# Page05_DDR4L_eMMC.net
KiCad netlist of a schematic drawn in Altium Designer
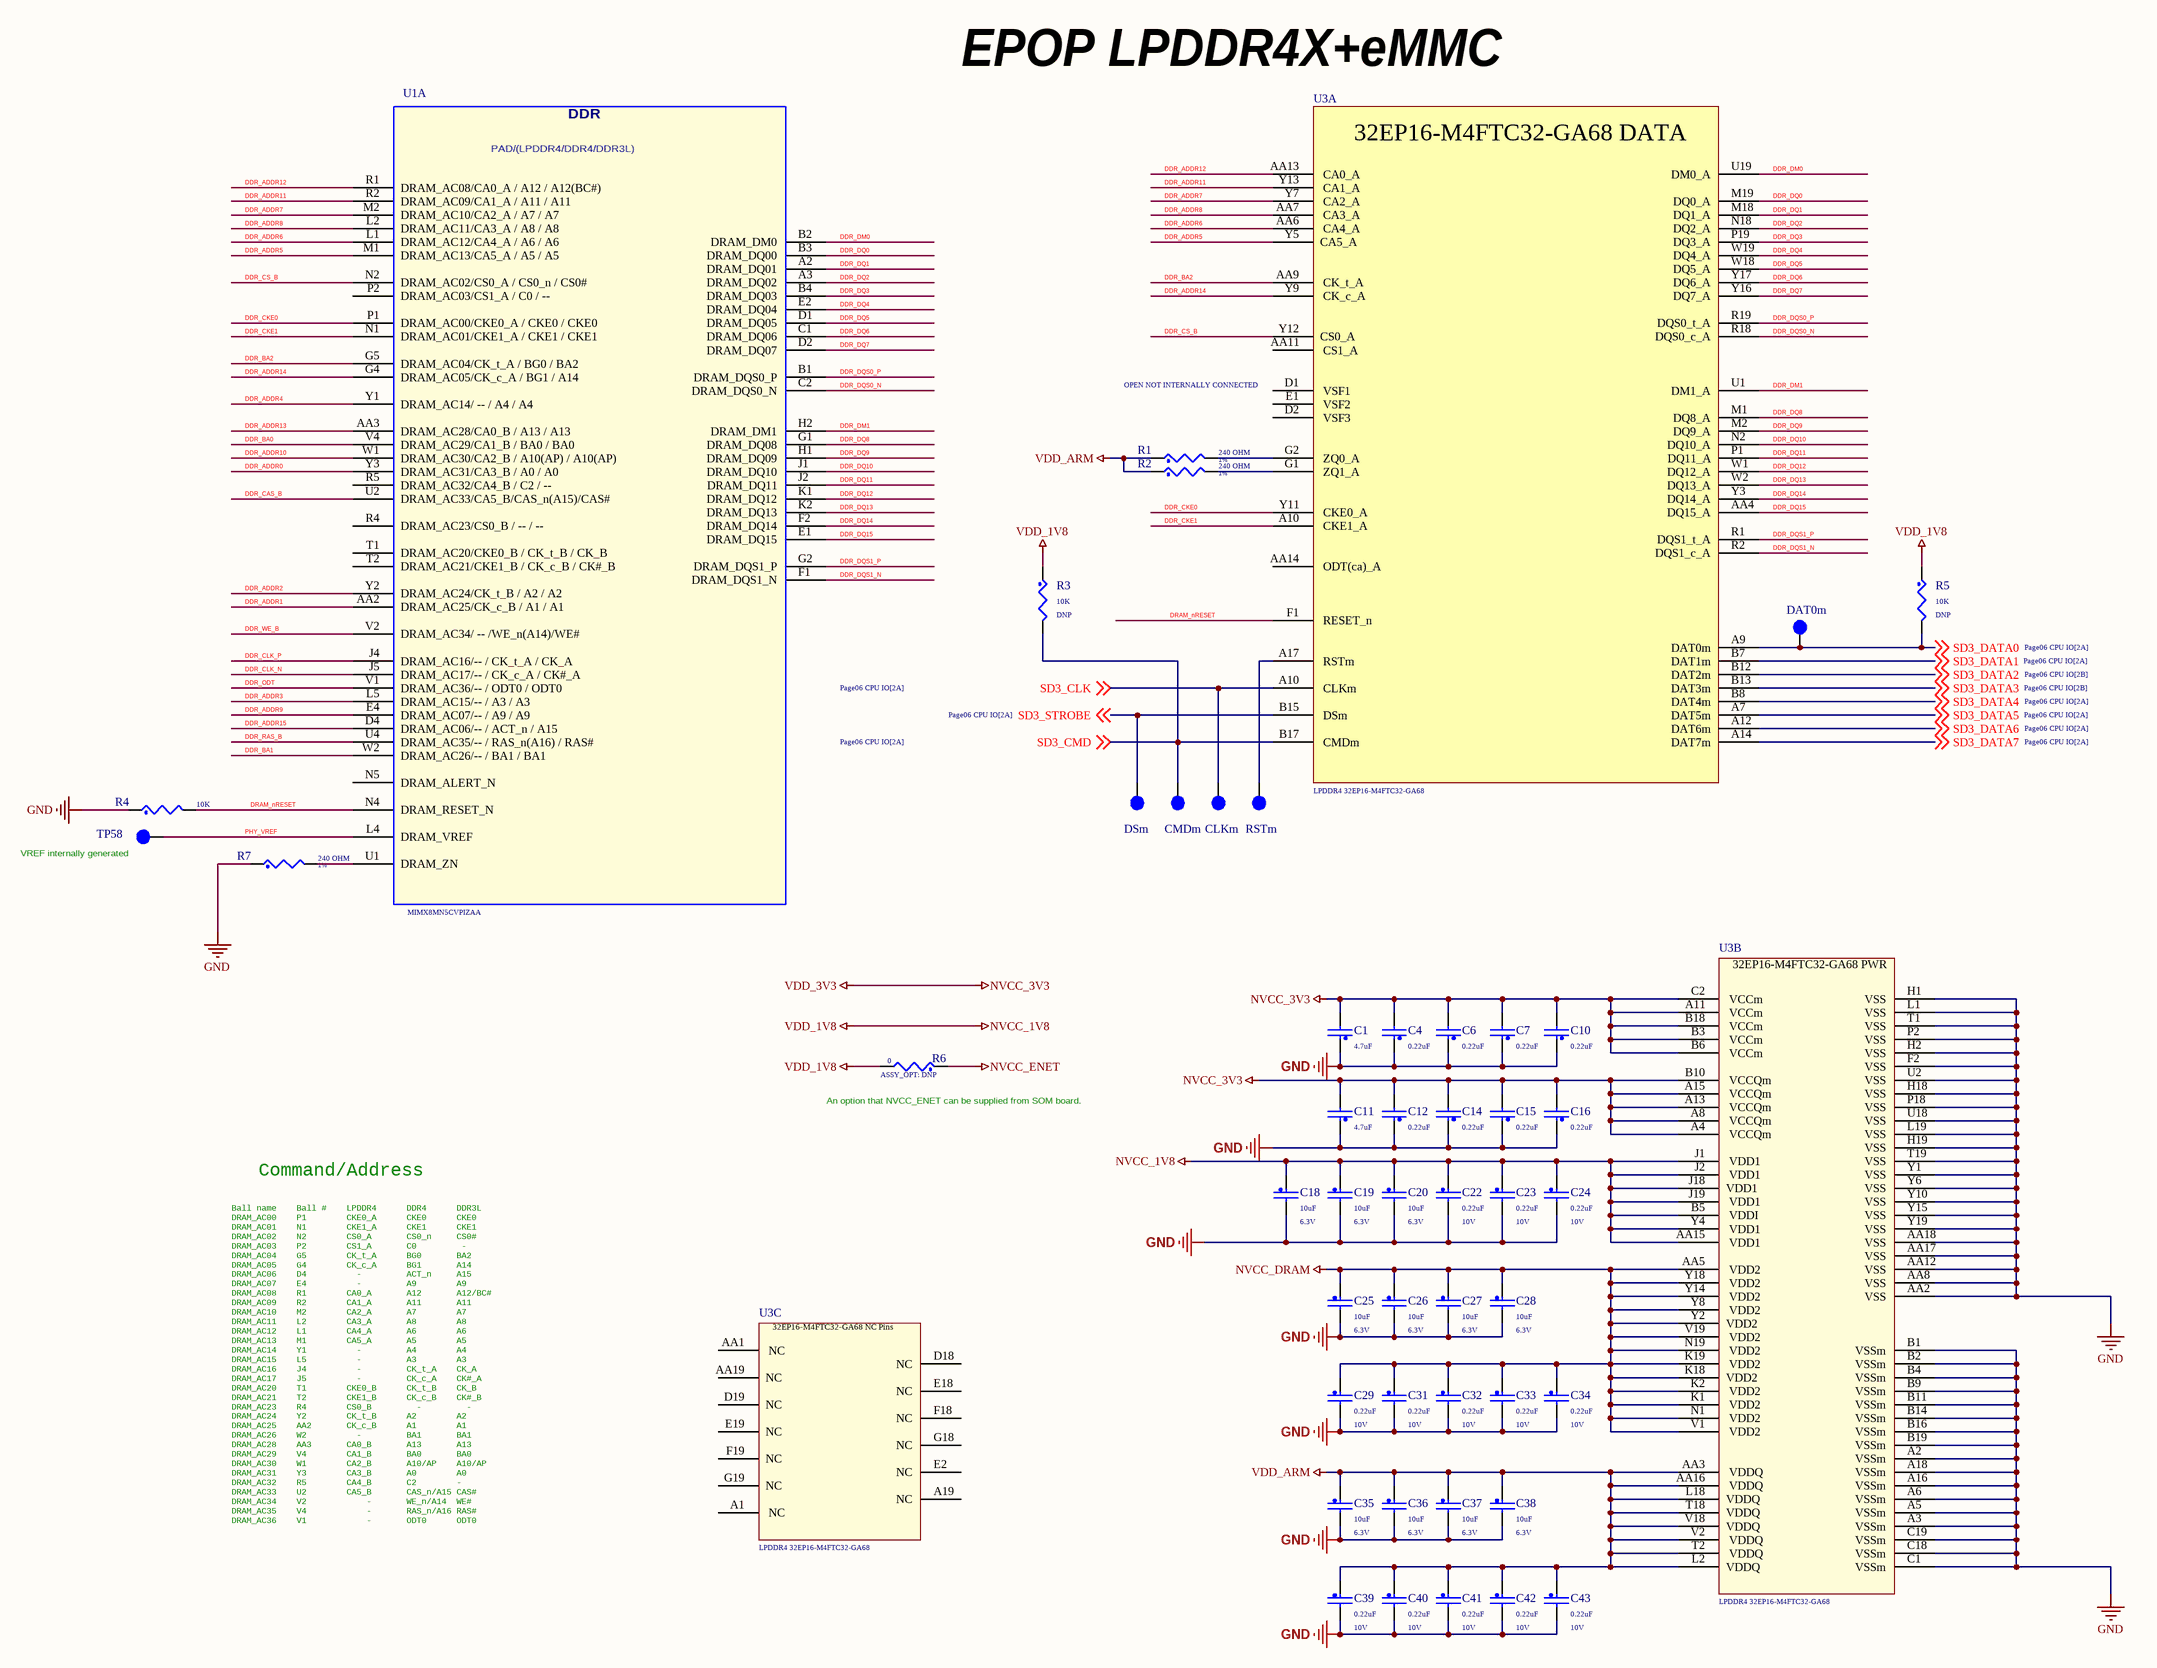
[diagram p0: Page05 DDR4L+eMMC.SchDoc]

(export (version "E")
  (design (tool "Eeschema 10.0.6"))
  (components
    (comp (ref "C1") (value "4.7uF") (footprint "0402_CC - C") (libsource (lib "AA_iMX8_M_") (part "CAP_NP")))
    (comp (ref "C4")
      (value "0.22uF")
      (footprint "0201_CC - C")
      (libsource (lib "AA_iMX8_M_") (part "CAP_NP"))
    )
    (comp (ref "C6")
      (value "0.22uF")
      (footprint "0201_CC - C")
      (libsource (lib "AA_iMX8_M_") (part "CAP_NP"))
    )
    (comp (ref "C7")
      (value "0.22uF")
      (footprint "0201_CC - C")
      (libsource (lib "AA_iMX8_M_") (part "CAP_NP"))
    )
    (comp (ref "C10")
      (value "0.22uF")
      (footprint "0201_CC - C")
      (libsource (lib "AA_iMX8_M_") (part "CAP_NP"))
    )
    (comp (ref "C11")
      (value "4.7uF")
      (footprint "0402_CC - C")
      (libsource (lib "AA_iMX8_M_") (part "CAP_NP"))
    )
    (comp (ref "C12")
      (value "0.22uF")
      (footprint "0201_CC - C")
      (libsource (lib "AA_iMX8_M_") (part "CAP_NP"))
    )
    (comp (ref "C14")
      (value "0.22uF")
      (footprint "0201_CC - C")
      (libsource (lib "AA_iMX8_M_") (part "CAP_NP"))
    )
    (comp (ref "C15")
      (value "0.22uF")
      (footprint "0201_CC - C")
      (libsource (lib "AA_iMX8_M_") (part "CAP_NP"))
    )
    (comp (ref "C16")
      (value "0.22uF")
      (footprint "0201_CC - C")
      (libsource (lib "AA_iMX8_M_") (part "CAP_NP"))
    )
    (comp (ref "C18")
      (value "10uF")
      (footprint "0402_CC - C")
      (fields (field (name "VOLTAGE") "6.3V"))
      (libsource (lib "AA_iMX8_M_") (part "CAP_NP"))
    )
    (comp (ref "C19")
      (value "10uF")
      (footprint "0402_CC - C")
      (fields (field (name "VOLTAGE") "6.3V"))
      (libsource (lib "AA_iMX8_M_") (part "CAP_NP"))
    )
    (comp (ref "C20")
      (value "10uF")
      (footprint "0402_CC - C")
      (fields (field (name "VOLTAGE") "6.3V"))
      (libsource (lib "AA_iMX8_M_") (part "CAP_NP"))
    )
    (comp (ref "C22")
      (value "0.22uF")
      (footprint "0201_CC - C")
      (fields (field (name "VOLTAGE") "10V"))
      (libsource (lib "AA_iMX8_M_") (part "CAP_NP"))
    )
    (comp (ref "C23")
      (value "0.22uF")
      (footprint "0201_CC - C")
      (fields (field (name "VOLTAGE") "10V"))
      (libsource (lib "AA_iMX8_M_") (part "CAP_NP"))
    )
    (comp (ref "C24")
      (value "0.22uF")
      (footprint "0201_CC - C")
      (fields (field (name "VOLTAGE") "10V"))
      (libsource (lib "AA_iMX8_M_") (part "CAP_NP"))
    )
    (comp (ref "C25")
      (value "10uF")
      (footprint "0402_CC - C")
      (fields (field (name "VOLTAGE") "6.3V"))
      (libsource (lib "AA_iMX8_M_") (part "CAP_NP"))
    )
    (comp (ref "C26")
      (value "10uF")
      (footprint "0402_CC - C")
      (fields (field (name "VOLTAGE") "6.3V"))
      (libsource (lib "AA_iMX8_M_") (part "CAP_NP"))
    )
    (comp (ref "C27")
      (value "10uF")
      (footprint "0402_CC - C")
      (fields (field (name "VOLTAGE") "6.3V"))
      (libsource (lib "AA_iMX8_M_") (part "CAP_NP"))
    )
    (comp (ref "C28")
      (value "10uF")
      (footprint "0402_CC - C")
      (fields (field (name "VOLTAGE") "6.3V"))
      (libsource (lib "AA_iMX8_M_") (part "CAP_NP"))
    )
    (comp (ref "C29")
      (value "0.22uF")
      (footprint "0201_CC - C")
      (fields (field (name "VOLTAGE") "10V"))
      (libsource (lib "AA_iMX8_M_") (part "CAP_NP"))
    )
    (comp (ref "C31")
      (value "0.22uF")
      (footprint "0201_CC - C")
      (fields (field (name "VOLTAGE") "10V"))
      (libsource (lib "AA_iMX8_M_") (part "CAP_NP"))
    )
    (comp (ref "C32")
      (value "0.22uF")
      (footprint "0201_CC - C")
      (fields (field (name "VOLTAGE") "10V"))
      (libsource (lib "AA_iMX8_M_") (part "CAP_NP"))
    )
    (comp (ref "C33")
      (value "0.22uF")
      (footprint "0201_CC - C")
      (fields (field (name "VOLTAGE") "10V"))
      (libsource (lib "AA_iMX8_M_") (part "CAP_NP"))
    )
    (comp (ref "C34")
      (value "0.22uF")
      (footprint "0201_CC - C")
      (fields (field (name "VOLTAGE") "10V"))
      (libsource (lib "AA_iMX8_M_") (part "CAP_NP"))
    )
    (comp (ref "C35")
      (value "10uF")
      (footprint "0402_CC - C")
      (fields (field (name "VOLTAGE") "6.3V"))
      (libsource (lib "AA_iMX8_M_") (part "CAP_NP"))
    )
    (comp (ref "C36")
      (value "10uF")
      (footprint "0402_CC - C")
      (fields (field (name "VOLTAGE") "6.3V"))
      (libsource (lib "AA_iMX8_M_") (part "CAP_NP"))
    )
    (comp (ref "C37")
      (value "10uF")
      (footprint "0402_CC - C")
      (fields (field (name "VOLTAGE") "6.3V"))
      (libsource (lib "AA_iMX8_M_") (part "CAP_NP"))
    )
    (comp (ref "C38")
      (value "10uF")
      (footprint "0402_CC - C")
      (fields (field (name "VOLTAGE") "6.3V"))
      (libsource (lib "AA_iMX8_M_") (part "CAP_NP"))
    )
    (comp (ref "C39")
      (value "0.22uF")
      (footprint "0201_CC - C")
      (fields (field (name "VOLTAGE") "10V"))
      (libsource (lib "AA_iMX8_M_") (part "CAP_NP"))
    )
    (comp (ref "C40")
      (value "0.22uF")
      (footprint "0201_CC - C")
      (fields (field (name "VOLTAGE") "10V"))
      (libsource (lib "AA_iMX8_M_") (part "CAP_NP"))
    )
    (comp (ref "C41")
      (value "0.22uF")
      (footprint "0201_CC - C")
      (fields (field (name "VOLTAGE") "10V"))
      (libsource (lib "AA_iMX8_M_") (part "CAP_NP"))
    )
    (comp (ref "C42")
      (value "0.22uF")
      (footprint "0201_CC - C")
      (fields (field (name "VOLTAGE") "10V"))
      (libsource (lib "AA_iMX8_M_") (part "CAP_NP"))
    )
    (comp (ref "C43")
      (value "0.22uF")
      (footprint "0201_CC - C")
      (fields (field (name "VOLTAGE") "10V"))
      (libsource (lib "AA_iMX8_M_") (part "CAP_NP"))
    )
    (comp (ref "CLKm")
      (value "tpad_020")
      (footprint "Test Pin")
      (description "TEST POINT PAD 0.5MM DIA SMT, NO PART TO ORDER")
      (libsource (lib "*") (part "TESTLOOP"))
    )
    (comp (ref "CMDm")
      (value "TPAD_015")
      (footprint "Test Pin")
      (description "TEST POINT PAD 15MIL DIA SMT, NO PART TO ORDER")
      (libsource (lib "*") (part "TESTLOOP"))
    )
    (comp (ref "DAT0m")
      (value "tpad_020")
      (footprint "Test Pin")
      (description "TEST POINT PAD 0.5MM DIA SMT, NO PART TO ORDER")
      (libsource (lib "*") (part "TESTLOOP"))
    )
    (comp (ref "DSm")
      (value "TPAD_015")
      (footprint "Test Pin")
      (description "TEST POINT PAD 15MIL DIA SMT, NO PART TO ORDER")
      (libsource (lib "*") (part "TESTLOOP"))
    )
    (comp (ref "R1")
      (value "240 OHM")
      (footprint "0201_RES")
      (description "RES MF 240 OHM 1/20W 1% 0201")
      (fields (field (name "VOLTAGE") "25V") (field (name "TOLERANCE") "1%"))
      (libsource (lib "*") (part "RES"))
    )
    (comp (ref "R2")
      (value "240 OHM")
      (footprint "0201_RES")
      (description "RES MF 240 OHM 1/20W 1% 0201")
      (fields (field (name "VOLTAGE") "25V") (field (name "TOLERANCE") "1%"))
      (libsource (lib "*") (part "RES"))
    )
    (comp (ref "R3")
      (value "10K")
      (footprint "0201_RES")
      (description "RES MF 10K 1/20W 5% 0201")
      (fields (field (name "ASSY_OPT") "DNP") (field (name "TOLERANCE") "5%"))
      (libsource (lib "*") (part "RES"))
    )
    (comp (ref "R4")
      (value "10K")
      (footprint "0201_RES")
      (description "RES MF 10K 1/20W 5% 0201")
      (fields (field (name "TOLERANCE") "5%"))
      (libsource (lib "*") (part "RES"))
    )
    (comp (ref "R5")
      (value "10K")
      (footprint "0201_RES")
      (description "RES MF 10K 1/20W 5% 0201")
      (fields (field (name "ASSY_OPT") "DNP") (field (name "TOLERANCE") "5%"))
      (libsource (lib "*") (part "RES"))
    )
    (comp (ref "R6")
      (value "0")
      (footprint "0402_CC_RES")
      (description "RES MF ZERO OHM 1/16W 5% 0402")
      (fields
        (field (name "ASSY_OPT") "DNP")
        (field (name "TOLERANCE") "5%")
        (field (name "VOLTAGE") "1/16W")
      )
      (libsource (lib "*") (part "RES"))
    )
    (comp (ref "R7")
      (value "240 OHM")
      (footprint "0201_RES")
      (description "RES MF 240 OHM 1/20W 1% 0201")
      (fields (field (name "VOLTAGE") "25V") (field (name "TOLERANCE") "1%"))
      (libsource (lib "*") (part "RES"))
    )
    (comp (ref "RSTm")
      (value "tpad_020")
      (footprint "Test Pin")
      (description "TEST POINT PAD 0.5MM DIA SMT, NO PART TO ORDER")
      (libsource (lib "*") (part "TESTLOOP"))
    )
    (comp (ref "TP58")
      (value "tpad_020")
      (footprint "Test Pin")
      (description "TEST POINT PAD 0.5MM DIA SMT, NO PART TO ORDER")
      (libsource (lib "*") (part "TESTLOOP"))
    )
    (comp (ref "U1")
      (value "MIMX8MN5CVPIZAA")
      (footprint "BGA306C50P21X21_1100X1100X101")
      (description "IC CPU QUAD CORTEX A53+M7 1.4GHZ -- BGA306")
      (libsource (lib "*") (part "MIMX8MN"))
    )
    (comp (ref "U3")
      (value "LPDDR4 32EP16-M4FTC32-GA68")
      (footprint "FBGA144C40P19X21_800X950X80")
      (libsource (lib "") (part "LPDDR4 32EP16-M4FTC32-GA68_1"))
    )
  )
  (nets
    (net (code "1") (name "/DDR_ADDR0") (class "Default")
      (node (ref "U1") (pin "Y3") (pinfunction "DRAM_AC31/CA3_B_/_A0_/_A0_Y3") (pintype "passive"))
    )
    (net (code "2") (name "/DDR_ADDR1") (class "Default")
      (node (ref "U1") (pin "AA2") (pinfunction "DRAM_AC25/CK_c_B_/_A1_/_A1_AA2") (pintype "passive"))
    )
    (net (code "3") (name "/DDR_ADDR2") (class "Default")
      (node (ref "U1") (pin "Y2") (pinfunction "DRAM_AC24/CK_t_B_/_A2_/_A2_Y2") (pintype "passive"))
    )
    (net (code "4") (name "/DDR_ADDR3") (class "Default")
      (node (ref "U1") (pin "L5") (pinfunction "DRAM_AC15/--_/_A3_/_A3_L5") (pintype "passive"))
    )
    (net (code "5") (name "/DDR_ADDR4") (class "Default")
      (node (ref "U1") (pin "Y1") (pinfunction "DRAM_AC14/_--_/_A4_/_A4_Y1") (pintype "passive"))
    )
    (net (code "6") (name "/DDR_ADDR5") (class "Default")
      (node (ref "U1") (pin "M1") (pinfunction "DRAM_AC13/CA5_A_/_A5_/_A5_M1") (pintype "passive"))
      (node (ref "U3") (pin "Y5") (pinfunction "CA5_A_Y5") (pintype "passive"))
    )
    (net (code "7") (name "/DDR_ADDR6") (class "Default")
      (node (ref "U1") (pin "L1") (pinfunction "DRAM_AC12/CA4_A_/_A6_/_A6_L1") (pintype "passive"))
      (node (ref "U3") (pin "AA6") (pinfunction "_CA4_A_AA6") (pintype "passive"))
    )
    (net (code "8") (name "/DDR_ADDR7") (class "Default")
      (node (ref "U1") (pin "M2") (pinfunction "DRAM_AC10/CA2_A_/_A7_/_A7_M2") (pintype "passive"))
      (node (ref "U3") (pin "Y7") (pinfunction "_CA2_A_Y7") (pintype "passive"))
    )
    (net (code "9") (name "/DDR_ADDR8") (class "Default")
      (node (ref "U1") (pin "L2") (pinfunction "DRAM_AC11/CA3_A_/_A8_/_A8_L2") (pintype "passive"))
      (node (ref "U3") (pin "AA7") (pinfunction "_CA3_A_AA7") (pintype "passive"))
    )
    (net (code "10") (name "/DDR_ADDR9") (class "Default")
      (node (ref "U1") (pin "E4") (pinfunction "DRAM_AC07/--_/_A9_/_A9_E4") (pintype "passive"))
    )
    (net (code "11") (name "/DDR_ADDR10") (class "Default")
      (node (ref "U1") (pin "W1") (pinfunction "DRAM_AC30/CA2_B_/_A10(AP)_/_A10(AP)_W1") (pintype "passive"))
    )
    (net (code "12") (name "/DDR_ADDR11") (class "Default")
      (node (ref "U1") (pin "R2") (pinfunction "DRAM_AC09/CA1_A_/_A11_/_A11_R2") (pintype "passive"))
      (node (ref "U3") (pin "Y13") (pinfunction "_CA1_A_Y13") (pintype "passive"))
    )
    (net (code "13") (name "/DDR_ADDR12") (class "Default")
      (node (ref "U1") (pin "R1") (pinfunction "DRAM_AC08/CA0_A_/_A12_/_A12(BC#)_R1") (pintype "passive"))
      (node (ref "U3") (pin "AA13") (pinfunction "_CA0_A_AA13") (pintype "passive"))
    )
    (net (code "14") (name "/DDR_ADDR13") (class "Default")
      (node (ref "U1") (pin "AA3") (pinfunction "DRAM_AC28/CA0_B_/_A13_/_A13_AA3") (pintype "passive"))
    )
    (net (code "15") (name "/DDR_ADDR14") (class "Default")
      (node (ref "U1") (pin "G4") (pinfunction "DRAM_AC05/CK_c_A_/_BG1_/_A14_G4") (pintype "passive"))
      (node (ref "U3") (pin "Y9") (pinfunction "_CK_c_A_Y9") (pintype "passive"))
    )
    (net (code "16") (name "/DDR_ADDR15") (class "Default")
      (node (ref "U1") (pin "D4") (pinfunction "DRAM_AC06/--_/_ACT_n_/_A15_D4") (pintype "passive"))
    )
    (net (code "17") (name "/DDR_BA0") (class "Default")
      (node (ref "U1") (pin "V4") (pinfunction "DRAM_AC29/CA1_B_/_BA0_/_BA0_V4") (pintype "passive"))
    )
    (net (code "18") (name "/DDR_BA1") (class "Default")
      (node (ref "U1") (pin "W2") (pinfunction "DRAM_AC26/--_/_BA1_/_BA1_W2") (pintype "passive"))
    )
    (net (code "19") (name "/DDR_BA2") (class "Default")
      (node (ref "U1") (pin "G5") (pinfunction "DRAM_AC04/CK_t_A_/_BG0_/_BA2_G5") (pintype "passive"))
      (node (ref "U3") (pin "AA9") (pinfunction "_CK_t_A_AA9") (pintype "passive"))
    )
    (net (code "20") (name "/DDR_CAS_B") (class "Default")
      (node (ref "U1") (pin "U2") (pinfunction "DRAM_AC33/CA5_B/CAS_n(A15)/CAS#_U2") (pintype "passive"))
    )
    (net (code "21") (name "/DDR_CKE0") (class "Default")
      (node (ref "U1") (pin "P1") (pinfunction "DRAM_AC00/CKE0_A_/_CKE0_/_CKE0_P1") (pintype "passive"))
      (node (ref "U3") (pin "Y11") (pinfunction "_CKE0_A_Y11") (pintype "passive"))
    )
    (net (code "22") (name "/DDR_CKE1") (class "Default")
      (node (ref "U1") (pin "N1") (pinfunction "DRAM_AC01/CKE1_A_/_CKE1_/_CKE1_N1") (pintype "passive"))
      (node (ref "U3") (pin "A10") (pinfunction "_CKE1_A_A10") (pintype "passive"))
    )
    (net (code "23") (name "/DDR_CLK_N") (class "Default")
      (node (ref "U1") (pin "J5") (pinfunction "DRAM_AC17/--_/_CK_c_A_/_CK#_A_J5") (pintype "passive"))
    )
    (net (code "24") (name "/DDR_CLK_P") (class "Default")
      (node (ref "U1") (pin "J4") (pinfunction "DRAM_AC16/--_/_CK_t_A_/_CK_A_J4") (pintype "passive"))
    )
    (net (code "25") (name "/DDR_CS_B") (class "Default")
      (node (ref "U1") (pin "N2") (pinfunction "DRAM_AC02/CS0_A_/_CS0_n_/_CS0#_N2") (pintype "passive"))
      (node (ref "U3") (pin "Y12") (pinfunction "CS0_A_Y12") (pintype "passive"))
    )
    (net (code "26") (name "/DDR_DM0") (class "Default")
      (node (ref "U1") (pin "B2") (pinfunction "DRAM_DM0_B2") (pintype "passive"))
      (node (ref "U3") (pin "U19") (pinfunction "_DM0_A_U19") (pintype "passive"))
    )
    (net (code "27") (name "/DDR_DM1") (class "Default")
      (node (ref "U1") (pin "H2") (pinfunction "DRAM_DM1_H2") (pintype "passive"))
      (node (ref "U3") (pin "U1") (pinfunction "_DM1_A_U1") (pintype "passive"))
    )
    (net (code "28") (name "/DDR_DQ0") (class "Default")
      (node (ref "U1") (pin "B3") (pinfunction "DRAM_DQ00_B3") (pintype "passive"))
      (node (ref "U3") (pin "M19") (pinfunction "_DQ0_A_M19") (pintype "passive"))
    )
    (net (code "29") (name "/DDR_DQ1") (class "Default")
      (node (ref "U1") (pin "A2") (pinfunction "DRAM_DQ01_A2") (pintype "passive"))
      (node (ref "U3") (pin "M18") (pinfunction "DQ1_A_M18") (pintype "passive"))
    )
    (net (code "30") (name "/DDR_DQ2") (class "Default")
      (node (ref "U1") (pin "A3") (pinfunction "DRAM_DQ02_A3") (pintype "passive"))
      (node (ref "U3") (pin "N18") (pinfunction "DQ2_A_N18") (pintype "passive"))
    )
    (net (code "31") (name "/DDR_DQ3") (class "Default")
      (node (ref "U1") (pin "B4") (pinfunction "DRAM_DQ03_B4") (pintype "passive"))
      (node (ref "U3") (pin "P19") (pinfunction "DQ3_A_P19") (pintype "passive"))
    )
    (net (code "32") (name "/DDR_DQ4") (class "Default")
      (node (ref "U1") (pin "E2") (pinfunction "DRAM_DQ04_E2") (pintype "passive"))
      (node (ref "U3") (pin "W19") (pinfunction "_DQ4_A_W19") (pintype "passive"))
    )
    (net (code "33") (name "/DDR_DQ5") (class "Default")
      (node (ref "U1") (pin "D1") (pinfunction "DRAM_DQ05_D1") (pintype "passive"))
      (node (ref "U3") (pin "W18") (pinfunction "DQ5_A_W18") (pintype "passive"))
    )
    (net (code "34") (name "/DDR_DQ6") (class "Default")
      (node (ref "U1") (pin "C1") (pinfunction "DRAM_DQ06_C1") (pintype "passive"))
      (node (ref "U3") (pin "Y17") (pinfunction "_DQ6_A_Y17") (pintype "passive"))
    )
    (net (code "35") (name "/DDR_DQ7") (class "Default")
      (node (ref "U1") (pin "D2") (pinfunction "DRAM_DQ07_D2") (pintype "passive"))
      (node (ref "U3") (pin "Y16") (pinfunction "_DQ7_A_Y16") (pintype "passive"))
    )
    (net (code "36") (name "/DDR_DQ8") (class "Default")
      (node (ref "U1") (pin "G1") (pinfunction "DRAM_DQ08_G1") (pintype "passive"))
      (node (ref "U3") (pin "M1") (pinfunction "_DQ8_A_M1") (pintype "passive"))
    )
    (net (code "37") (name "/DDR_DQ9") (class "Default")
      (node (ref "U1") (pin "H1") (pinfunction "DRAM_DQ09_H1") (pintype "passive"))
      (node (ref "U3") (pin "M2") (pinfunction "_DQ9_A_M2") (pintype "passive"))
    )
    (net (code "38") (name "/DDR_DQ10") (class "Default")
      (node (ref "U1") (pin "J1") (pinfunction "DRAM_DQ10_J1") (pintype "passive"))
      (node (ref "U3") (pin "N2") (pinfunction "_DQ10_A_N2") (pintype "passive"))
    )
    (net (code "39") (name "/DDR_DQ11") (class "Default")
      (node (ref "U1") (pin "J2") (pinfunction "DRAM_DQ11_J2") (pintype "passive"))
      (node (ref "U3") (pin "P1") (pinfunction "_DQ11_A_P1") (pintype "passive"))
    )
    (net (code "40") (name "/DDR_DQ12") (class "Default")
      (node (ref "U1") (pin "K1") (pinfunction "DRAM_DQ12_K1") (pintype "passive"))
      (node (ref "U3") (pin "W1") (pinfunction "_DQ12_A_W1") (pintype "passive"))
    )
    (net (code "41") (name "/DDR_DQ13") (class "Default")
      (node (ref "U1") (pin "K2") (pinfunction "DRAM_DQ13_K2") (pintype "passive"))
      (node (ref "U3") (pin "W2") (pinfunction "_DQ13_A_W2") (pintype "passive"))
    )
    (net (code "42") (name "/DDR_DQ14") (class "Default")
      (node (ref "U1") (pin "F2") (pinfunction "DRAM_DQ14_F2") (pintype "passive"))
      (node (ref "U3") (pin "Y3") (pinfunction "_DQ14_A_Y3") (pintype "passive"))
    )
    (net (code "43") (name "/DDR_DQ15") (class "Default")
      (node (ref "U1") (pin "E1") (pinfunction "DRAM_DQ15_E1") (pintype "passive"))
      (node (ref "U3") (pin "AA4") (pinfunction "_DQ15_A_AA4") (pintype "passive"))
    )
    (net (code "44") (name "/DDR_DQS0_N") (class "Default")
      (node (ref "U1") (pin "C2") (pinfunction "DRAM_DQS0_N_C2") (pintype "passive"))
      (node (ref "U3") (pin "R18") (pinfunction "DQS0_c_A_R18") (pintype "passive"))
    )
    (net (code "45") (name "/DDR_DQS0_P") (class "Default")
      (node (ref "U1") (pin "B1") (pinfunction "DRAM_DQS0_P_B1") (pintype "passive"))
      (node (ref "U3") (pin "R19") (pinfunction "_DQS0_t_A_R19") (pintype "passive"))
    )
    (net (code "46") (name "/DDR_DQS1_N") (class "Default")
      (node (ref "U1") (pin "F1") (pinfunction "DRAM_DQS1_N_F1") (pintype "passive"))
      (node (ref "U3") (pin "R2") (pinfunction "_DQS1_c_A_R2") (pintype "passive"))
    )
    (net (code "47") (name "/DDR_DQS1_P") (class "Default")
      (node (ref "U1") (pin "G2") (pinfunction "DRAM_DQS1_P_G2") (pintype "passive"))
      (node (ref "U3") (pin "R1") (pinfunction "_DQS1_t_A_R1") (pintype "passive"))
    )
    (net (code "48") (name "/DDR_ODT") (class "Default")
      (node (ref "U1") (pin "V1") (pinfunction "DRAM_AC36/--_/_ODT0_/_ODT0_V1") (pintype "passive"))
    )
    (net (code "49") (name "/DDR_RAS_B") (class "Default")
      (node (ref "U1") (pin "U4") (pinfunction "DRAM_AC35/--_/_RAS_n(A16)_/_RAS#_U4") (pintype "passive"))
    )
    (net (code "50") (name "/DDR_WE_B") (class "Default")
      (node (ref "U1") (pin "V2") (pinfunction "DRAM_AC34/_--_/WE_n(A14)/WE#_V2") (pintype "passive"))
    )
    (net (code "51") (name "/DRAM_nRESET") (class "Default")
      (node (ref "R4") (pin "2") (pinfunction "2_2") (pintype "passive"))
      (node (ref "U1") (pin "N4") (pinfunction "DRAM_RESET_N_N4") (pintype "passive"))
      (node (ref "U3") (pin "F1") (pinfunction "_RESET_n_F1") (pintype "passive"))
    )
    (net (code "52") (name "/PHY_VREF") (class "Default")
      (node (ref "TP58") (pin "1") (pinfunction "Pin1_1") (pintype "passive"))
      (node (ref "U1") (pin "L4") (pinfunction "DRAM_VREF_L4") (pintype "passive"))
    )
    (net (code "53") (name "GND") (class "Default")
      (node (ref "C1") (pin "1") (pinfunction "1_1") (pintype "passive"))
      (node (ref "C10") (pin "1") (pinfunction "1_1") (pintype "passive"))
      (node (ref "C11") (pin "1") (pinfunction "1_1") (pintype "passive"))
      (node (ref "C12") (pin "1") (pinfunction "1_1") (pintype "passive"))
      (node (ref "C14") (pin "1") (pinfunction "1_1") (pintype "passive"))
      (node (ref "C15") (pin "1") (pinfunction "1_1") (pintype "passive"))
      (node (ref "C16") (pin "1") (pinfunction "1_1") (pintype "passive"))
      (node (ref "C18") (pin "2") (pinfunction "2_2") (pintype "passive"))
      (node (ref "C19") (pin "2") (pinfunction "2_2") (pintype "passive"))
      (node (ref "C20") (pin "2") (pinfunction "2_2") (pintype "passive"))
      (node (ref "C22") (pin "2") (pinfunction "2_2") (pintype "passive"))
      (node (ref "C23") (pin "2") (pinfunction "2_2") (pintype "passive"))
      (node (ref "C24") (pin "2") (pinfunction "2_2") (pintype "passive"))
      (node (ref "C25") (pin "2") (pinfunction "2_2") (pintype "passive"))
      (node (ref "C26") (pin "2") (pinfunction "2_2") (pintype "passive"))
      (node (ref "C27") (pin "2") (pinfunction "2_2") (pintype "passive"))
      (node (ref "C28") (pin "2") (pinfunction "2_2") (pintype "passive"))
      (node (ref "C29") (pin "2") (pinfunction "2_2") (pintype "passive"))
      (node (ref "C31") (pin "2") (pinfunction "2_2") (pintype "passive"))
      (node (ref "C32") (pin "2") (pinfunction "2_2") (pintype "passive"))
      (node (ref "C33") (pin "2") (pinfunction "2_2") (pintype "passive"))
      (node (ref "C34") (pin "2") (pinfunction "2_2") (pintype "passive"))
      (node (ref "C35") (pin "2") (pinfunction "2_2") (pintype "passive"))
      (node (ref "C36") (pin "2") (pinfunction "2_2") (pintype "passive"))
      (node (ref "C37") (pin "2") (pinfunction "2_2") (pintype "passive"))
      (node (ref "C38") (pin "2") (pinfunction "2_2") (pintype "passive"))
      (node (ref "C39") (pin "2") (pinfunction "2_2") (pintype "passive"))
      (node (ref "C4") (pin "1") (pinfunction "1_1") (pintype "passive"))
      (node (ref "C40") (pin "2") (pinfunction "2_2") (pintype "passive"))
      (node (ref "C41") (pin "2") (pinfunction "2_2") (pintype "passive"))
      (node (ref "C42") (pin "2") (pinfunction "2_2") (pintype "passive"))
      (node (ref "C43") (pin "2") (pinfunction "2_2") (pintype "passive"))
      (node (ref "C6") (pin "1") (pinfunction "1_1") (pintype "passive"))
      (node (ref "C7") (pin "1") (pinfunction "1_1") (pintype "passive"))
      (node (ref "R4") (pin "1") (pinfunction "1_1") (pintype "passive"))
      (node (ref "R7") (pin "1") (pinfunction "1_1") (pintype "passive"))
      (node (ref "U3") (pin "A16") (pinfunction "_VSSm_A16") (pintype "power_in"))
      (node (ref "U3") (pin "A18") (pinfunction "_VSSm_A18") (pintype "power_in"))
      (node (ref "U3") (pin "A2") (pinfunction "_VSSm_A2") (pintype "power_in"))
      (node (ref "U3") (pin "A3") (pinfunction "VSSm_A3") (pintype "power_in"))
      (node (ref "U3") (pin "A5") (pinfunction "_VSSm_A5") (pintype "power_in"))
      (node (ref "U3") (pin "A6") (pinfunction "_VSSm_A6") (pintype "power_in"))
      (node (ref "U3") (pin "AA12") (pinfunction "_VSS_AA12") (pintype "power_in"))
      (node (ref "U3") (pin "AA17") (pinfunction "_VSS_AA17") (pintype "power_in"))
      (node (ref "U3") (pin "AA18") (pinfunction "VSS_AA18") (pintype "power_in"))
      (node (ref "U3") (pin "AA2") (pinfunction "VSS_AA2") (pintype "power_in"))
      (node (ref "U3") (pin "AA8") (pinfunction "_VSS_AA8") (pintype "power_in"))
      (node (ref "U3") (pin "B1") (pinfunction "_VSSm_B1") (pintype "power_in"))
      (node (ref "U3") (pin "B11") (pinfunction "_VSSm_B11") (pintype "power_in"))
      (node (ref "U3") (pin "B14") (pinfunction "_VSSm_B14") (pintype "power_in"))
      (node (ref "U3") (pin "B16") (pinfunction "_VSSm_B16") (pintype "power_in"))
      (node (ref "U3") (pin "B19") (pinfunction "_VSSm_B19") (pintype "power_in"))
      (node (ref "U3") (pin "B2") (pinfunction "_VSSm_B2") (pintype "power_in"))
      (node (ref "U3") (pin "B4") (pinfunction "_VSSm_B4") (pintype "power_in"))
      (node (ref "U3") (pin "B9") (pinfunction "_VSSm_B9") (pintype "power_in"))
      (node (ref "U3") (pin "C1") (pinfunction "_VSSm_C1") (pintype "power_in"))
      (node (ref "U3") (pin "C18") (pinfunction "VSSm_C18") (pintype "power_in"))
      (node (ref "U3") (pin "C19") (pinfunction "_VSSm_C19") (pintype "power_in"))
      (node (ref "U3") (pin "F2") (pinfunction "_VSS_F2") (pintype "power_in"))
      (node (ref "U3") (pin "H1") (pinfunction "_VSS_H1") (pintype "power_in"))
      (node (ref "U3") (pin "H18") (pinfunction "VSS_H18") (pintype "power_in"))
      (node (ref "U3") (pin "H19") (pinfunction "VSS_H19") (pintype "power_in"))
      (node (ref "U3") (pin "H2") (pinfunction "VSS_H2") (pintype "power_in"))
      (node (ref "U3") (pin "L1") (pinfunction "_VSS_L1") (pintype "power_in"))
      (node (ref "U3") (pin "L19") (pinfunction "VSS_L19") (pintype "power_in"))
      (node (ref "U3") (pin "P18") (pinfunction "VSS_P18") (pintype "power_in"))
      (node (ref "U3") (pin "P2") (pinfunction "_VSS_P2") (pintype "power_in"))
      (node (ref "U3") (pin "T1") (pinfunction "_VSS_T1") (pintype "power_in"))
      (node (ref "U3") (pin "T19") (pinfunction "VSS_T19") (pintype "power_in"))
      (node (ref "U3") (pin "U18") (pinfunction "VSS_U18") (pintype "power_in"))
      (node (ref "U3") (pin "U2") (pinfunction "_VSS_U2") (pintype "power_in"))
      (node (ref "U3") (pin "Y1") (pinfunction "_VSS_Y1") (pintype "power_in"))
      (node (ref "U3") (pin "Y10") (pinfunction "_VSS_Y10") (pintype "power_in"))
      (node (ref "U3") (pin "Y15") (pinfunction "_VSS_Y15") (pintype "power_in"))
      (node (ref "U3") (pin "Y19") (pinfunction "VSS_Y19") (pintype "power_in"))
      (node (ref "U3") (pin "Y6") (pinfunction "_VSS_Y6") (pintype "power_in"))
    )
    (net (code "54") (name "NVCC_1V8") (class "Default")
      (node (ref "C18") (pin "1") (pinfunction "1_1") (pintype "passive"))
      (node (ref "C19") (pin "1") (pinfunction "1_1") (pintype "passive"))
      (node (ref "C20") (pin "1") (pinfunction "1_1") (pintype "passive"))
      (node (ref "C22") (pin "1") (pinfunction "1_1") (pintype "passive"))
      (node (ref "C23") (pin "1") (pinfunction "1_1") (pintype "passive"))
      (node (ref "C24") (pin "1") (pinfunction "1_1") (pintype "passive"))
      (node (ref "R3") (pin "1") (pinfunction "1_1") (pintype "passive"))
      (node (ref "R5") (pin "1") (pinfunction "1_1") (pintype "passive"))
      (node (ref "R6") (pin "2") (pinfunction "2_2") (pintype "passive"))
      (node (ref "U3") (pin "AA15") (pinfunction "_VDD1_AA15") (pintype "power_in"))
      (node (ref "U3") (pin "B5") (pinfunction "_VDDI_B5") (pintype "power_in"))
      (node (ref "U3") (pin "J1") (pinfunction "_VDD1_J1") (pintype "power_in"))
      (node (ref "U3") (pin "J18") (pinfunction "VDD1_J18") (pintype "power_in"))
      (node (ref "U3") (pin "J19") (pinfunction "_VDD1_J19") (pintype "power_in"))
      (node (ref "U3") (pin "J2") (pinfunction "_VDD1_J2") (pintype "power_in"))
      (node (ref "U3") (pin "Y4") (pinfunction "_VDD1_Y4") (pintype "power_in"))
    )
    (net (code "55") (name "NVCC_3V3") (class "Default")
      (node (ref "C1") (pin "2") (pinfunction "2_2") (pintype "passive"))
      (node (ref "C10") (pin "2") (pinfunction "2_2") (pintype "passive"))
      (node (ref "C11") (pin "2") (pinfunction "2_2") (pintype "passive"))
      (node (ref "C12") (pin "2") (pinfunction "2_2") (pintype "passive"))
      (node (ref "C14") (pin "2") (pinfunction "2_2") (pintype "passive"))
      (node (ref "C15") (pin "2") (pinfunction "2_2") (pintype "passive"))
      (node (ref "C16") (pin "2") (pinfunction "2_2") (pintype "passive"))
      (node (ref "C4") (pin "2") (pinfunction "2_2") (pintype "passive"))
      (node (ref "C6") (pin "2") (pinfunction "2_2") (pintype "passive"))
      (node (ref "C7") (pin "2") (pinfunction "2_2") (pintype "passive"))
      (node (ref "U3") (pin "A11") (pinfunction "_VCCm_A11") (pintype "power_in"))
      (node (ref "U3") (pin "A13") (pinfunction "_VCCQm_A13") (pintype "power_in"))
      (node (ref "U3") (pin "A15") (pinfunction "_VCCQm_A15") (pintype "power_in"))
      (node (ref "U3") (pin "A4") (pinfunction "_VCCQm_A4") (pintype "power_in"))
      (node (ref "U3") (pin "A8") (pinfunction "_VCCQm_A8") (pintype "power_in"))
      (node (ref "U3") (pin "B10") (pinfunction "_VCCQm_B10") (pintype "power_in"))
      (node (ref "U3") (pin "B18") (pinfunction "_VCCm_B18") (pintype "power_in"))
      (node (ref "U3") (pin "B3") (pinfunction "_VCCm_B3") (pintype "power_in"))
      (node (ref "U3") (pin "B6") (pinfunction "_VCCm_B6") (pintype "power_in"))
      (node (ref "U3") (pin "C2") (pinfunction "_VCCm_C2") (pintype "power_in"))
    )
    (net (code "56") (name "NVCC_DRAM") (class "Default")
      (node (ref "C25") (pin "1") (pinfunction "1_1") (pintype "passive"))
      (node (ref "C26") (pin "1") (pinfunction "1_1") (pintype "passive"))
      (node (ref "C27") (pin "1") (pinfunction "1_1") (pintype "passive"))
      (node (ref "C28") (pin "1") (pinfunction "1_1") (pintype "passive"))
      (node (ref "C29") (pin "1") (pinfunction "1_1") (pintype "passive"))
      (node (ref "C31") (pin "1") (pinfunction "1_1") (pintype "passive"))
      (node (ref "C32") (pin "1") (pinfunction "1_1") (pintype "passive"))
      (node (ref "C33") (pin "1") (pinfunction "1_1") (pintype "passive"))
      (node (ref "C34") (pin "1") (pinfunction "1_1") (pintype "passive"))
      (node (ref "U3") (pin "AA5") (pinfunction "_VDD2_AA5") (pintype "power_in"))
      (node (ref "U3") (pin "K1") (pinfunction "_VDD2_K1") (pintype "power_in"))
      (node (ref "U3") (pin "K18") (pinfunction "VDD2_K18") (pintype "power_in"))
      (node (ref "U3") (pin "K19") (pinfunction "_VDD2_K19") (pintype "power_in"))
      (node (ref "U3") (pin "K2") (pinfunction "_VDD2_K2") (pintype "power_in"))
      (node (ref "U3") (pin "N1") (pinfunction "_VDD2_N1") (pintype "power_in"))
      (node (ref "U3") (pin "N19") (pinfunction "_VDD2_N19") (pintype "power_in"))
      (node (ref "U3") (pin "V1") (pinfunction "_VDD2_V1") (pintype "power_in"))
      (node (ref "U3") (pin "V19") (pinfunction "_VDD2_V19") (pintype "power_in"))
      (node (ref "U3") (pin "Y14") (pinfunction "_VDD2_Y14") (pintype "power_in"))
      (node (ref "U3") (pin "Y18") (pinfunction "_VDD2_Y18") (pintype "power_in"))
      (node (ref "U3") (pin "Y2") (pinfunction "VDD2_Y2") (pintype "power_in"))
      (node (ref "U3") (pin "Y8") (pinfunction "_VDD2_Y8") (pintype "power_in"))
    )
    (net (code "57") (name "NVCC_ENET") (class "Default")
      (node (ref "R6") (pin "1") (pinfunction "1_1") (pintype "passive"))
    )
    (net (code "58") (name "Net-(RSTm-Pin1)") (class "Default")
      (node (ref "RSTm") (pin "1") (pinfunction "Pin1_1") (pintype "passive"))
      (node (ref "U3") (pin "A17") (pinfunction "_RSTm_A17") (pintype "passive"))
    )
    (net (code "59") (name "Net-(U1A-DRAM_ZN)") (class "Default")
      (node (ref "R7") (pin "2") (pinfunction "2_2") (pintype "passive"))
      (node (ref "U1") (pin "U1") (pinfunction "DRAM_ZN_U1") (pintype "passive"))
    )
    (net (code "60") (name "Net-(U3A-_ZQ0_A)") (class "Default")
      (node (ref "R1") (pin "2") (pinfunction "2_2") (pintype "passive"))
      (node (ref "U3") (pin "G2") (pinfunction "_ZQ0_A_G2") (pintype "passive"))
    )
    (net (code "61") (name "Net-(U3A-_ZQ1_A)") (class "Default")
      (node (ref "R2") (pin "2") (pinfunction "2_2") (pintype "passive"))
      (node (ref "U3") (pin "G1") (pinfunction "_ZQ1_A_G1") (pintype "passive"))
    )
    (net (code "62") (name "SD3_CLK") (class "Default")
      (node (ref "CLKm") (pin "1") (pinfunction "Pin1_1") (pintype "passive"))
      (node (ref "U3") (pin "A10") (pinfunction "_CLKm_A10") (pintype "passive"))
    )
    (net (code "63") (name "SD3_CMD") (class "Default")
      (node (ref "CMDm") (pin "1") (pinfunction "Pin1_1") (pintype "passive"))
      (node (ref "R3") (pin "2") (pinfunction "2_2") (pintype "passive"))
      (node (ref "U3") (pin "B17") (pinfunction "_CMDm_B17") (pintype "passive"))
    )
    (net (code "64") (name "SD3_DATA0") (class "Default")
      (node (ref "DAT0m") (pin "1") (pinfunction "Pin1_1") (pintype "passive"))
      (node (ref "R5") (pin "2") (pinfunction "2_2") (pintype "passive"))
      (node (ref "U3") (pin "A9") (pinfunction "_DAT0m_A9") (pintype "passive"))
    )
    (net (code "65") (name "SD3_DATA1") (class "Default")
      (node (ref "U3") (pin "B7") (pinfunction "DAT1m_B7") (pintype "passive"))
    )
    (net (code "66") (name "SD3_DATA2") (class "Default")
      (node (ref "U3") (pin "B12") (pinfunction "_DAT2m_B12") (pintype "passive"))
    )
    (net (code "67") (name "SD3_DATA3") (class "Default")
      (node (ref "U3") (pin "B13") (pinfunction "_DAT3m_B13") (pintype "passive"))
    )
    (net (code "68") (name "SD3_DATA4") (class "Default")
      (node (ref "U3") (pin "B8") (pinfunction "_DAT4m_B8") (pintype "passive"))
    )
    (net (code "69") (name "SD3_DATA5") (class "Default")
      (node (ref "U3") (pin "A7") (pinfunction "_DAT5m_A7") (pintype "passive"))
    )
    (net (code "70") (name "SD3_DATA6") (class "Default")
      (node (ref "U3") (pin "A12") (pinfunction "_DAT6m_A12") (pintype "passive"))
    )
    (net (code "71") (name "SD3_DATA7") (class "Default")
      (node (ref "U3") (pin "A14") (pinfunction "_DAT7m_A14") (pintype "passive"))
    )
    (net (code "72") (name "SD3_STROBE") (class "Default")
      (node (ref "DSm") (pin "1") (pinfunction "Pin1_1") (pintype "passive"))
      (node (ref "U3") (pin "B15") (pinfunction "_DSm_B15") (pintype "passive"))
    )
    (net (code "73") (name "VDD_ARM") (class "Default")
      (node (ref "C35") (pin "1") (pinfunction "1_1") (pintype "passive"))
      (node (ref "C36") (pin "1") (pinfunction "1_1") (pintype "passive"))
      (node (ref "C37") (pin "1") (pinfunction "1_1") (pintype "passive"))
      (node (ref "C38") (pin "1") (pinfunction "1_1") (pintype "passive"))
      (node (ref "C39") (pin "1") (pinfunction "1_1") (pintype "passive"))
      (node (ref "C40") (pin "1") (pinfunction "1_1") (pintype "passive"))
      (node (ref "C41") (pin "1") (pinfunction "1_1") (pintype "passive"))
      (node (ref "C42") (pin "1") (pinfunction "1_1") (pintype "passive"))
      (node (ref "C43") (pin "1") (pinfunction "1_1") (pintype "passive"))
      (node (ref "R1") (pin "1") (pinfunction "1_1") (pintype "passive"))
      (node (ref "R2") (pin "1") (pinfunction "1_1") (pintype "passive"))
      (node (ref "U3") (pin "AA16") (pinfunction "_VDDQ_AA16") (pintype "power_in"))
      (node (ref "U3") (pin "AA3") (pinfunction "_VDDQ_AA3") (pintype "power_in"))
      (node (ref "U3") (pin "L18") (pinfunction "VDDQ_L18") (pintype "power_in"))
      (node (ref "U3") (pin "L2") (pinfunction "VDDQ_L2") (pintype "power_in"))
      (node (ref "U3") (pin "T18") (pinfunction "VDDQ_T18") (pintype "power_in"))
      (node (ref "U3") (pin "T2") (pinfunction "_VDDQ_T2") (pintype "power_in"))
      (node (ref "U3") (pin "V18") (pinfunction "VDDQ_V18") (pintype "power_in"))
      (node (ref "U3") (pin "V2") (pinfunction "_VDDQ_V2") (pintype "power_in"))
    )
    (net (code "74") (name "unconnected-(U1A-DRAM_AC03{slash}CS1_A_{slash}_C0_{slash}_---PadP2)") (class "Default")
      (node (ref "U1") (pin "P2") (pinfunction "DRAM_AC03/CS1_A_/_C0_/_--_P2") (pintype "passive"))
    )
    (net (code "75") (name "unconnected-(U1A-DRAM_AC20{slash}CKE0_B_{slash}_CK_t_B_{slash}_CK_B-PadT1)") (class "Default")
      (node (ref "U1") (pin "T1") (pinfunction "DRAM_AC20/CKE0_B_/_CK_t_B_/_CK_B_T1") (pintype "passive"))
    )
    (net (code "76") (name "unconnected-(U1A-DRAM_AC21{slash}CKE1_B_{slash}_CK_c_B_{slash}_CK#_B-PadT2)") (class "Default")
      (node (ref "U1") (pin "T2") (pinfunction "DRAM_AC21/CKE1_B_/_CK_c_B_/_CK#_B_T2") (pintype "passive"))
    )
    (net (code "77") (name "unconnected-(U1A-DRAM_AC23{slash}CS0_B_{slash}_--_{slash}_---PadR4)") (class "Default")
      (node (ref "U1") (pin "R4") (pinfunction "DRAM_AC23/CS0_B_/_--_/_--_R4") (pintype "passive"))
    )
    (net (code "78") (name "unconnected-(U1A-DRAM_AC32{slash}CA4_B_{slash}_C2_{slash}_---PadR5)") (class "Default")
      (node (ref "U1") (pin "R5") (pinfunction "DRAM_AC32/CA4_B_/_C2_/_--_R5") (pintype "passive"))
    )
    (net (code "79") (name "unconnected-(U1A-DRAM_ALERT_N-PadN5)") (class "Default")
      (node (ref "U1") (pin "N5") (pinfunction "DRAM_ALERT_N_N5") (pintype "passive"))
    )
    (net (code "80") (name "unconnected-(U3A-_CS1_A-PadAA11)") (class "Default")
      (node (ref "U3") (pin "AA11") (pinfunction "_CS1_A_AA11") (pintype "passive"))
    )
    (net (code "81") (name "unconnected-(U3A-_ODT(ca)_A-PadAA14)") (class "Default")
      (node (ref "U3") (pin "AA14") (pinfunction "_ODT(ca)_A_AA14") (pintype "passive"))
    )
    (net (code "82") (name "unconnected-(U3A-_VSF1-PadD1)") (class "Default")
      (node (ref "U3") (pin "D1") (pinfunction "_VSF1_D1") (pintype "passive"))
    )
    (net (code "83") (name "unconnected-(U3A-_VSF2-PadE1)") (class "Default")
      (node (ref "U3") (pin "E1") (pinfunction "_VSF2_E1") (pintype "passive"))
    )
    (net (code "84") (name "unconnected-(U3A-_VSF3-PadD2)") (class "Default")
      (node (ref "U3") (pin "D2") (pinfunction "_VSF3_D2") (pintype "passive"))
    )
    (net (code "85") (name "unconnected-(U3C-NC-PadA19)") (class "Default")
      (node (ref "U3") (pin "A19") (pinfunction "NC_A19") (pintype "passive"))
    )
    (net (code "86") (name "unconnected-(U3C-NC-PadAA19)") (class "Default")
      (node (ref "U3") (pin "AA19") (pinfunction "NC_AA19") (pintype "passive"))
    )
    (net (code "87") (name "unconnected-(U3C-NC-PadD18)") (class "Default")
      (node (ref "U3") (pin "D18") (pinfunction "NC_D18") (pintype "passive"))
    )
    (net (code "88") (name "unconnected-(U3C-NC-PadD19)") (class "Default")
      (node (ref "U3") (pin "D19") (pinfunction "NC_D19") (pintype "passive"))
    )
    (net (code "89") (name "unconnected-(U3C-NC-PadE2)") (class "Default")
      (node (ref "U3") (pin "E2") (pinfunction "NC_E2") (pintype "passive"))
    )
    (net (code "90") (name "unconnected-(U3C-NC-PadE18)") (class "Default")
      (node (ref "U3") (pin "E18") (pinfunction "NC_E18") (pintype "passive"))
    )
    (net (code "91") (name "unconnected-(U3C-NC-PadE19)") (class "Default")
      (node (ref "U3") (pin "E19") (pinfunction "NC_E19") (pintype "passive"))
    )
    (net (code "92") (name "unconnected-(U3C-NC-PadF18)") (class "Default")
      (node (ref "U3") (pin "F18") (pinfunction "NC_F18") (pintype "passive"))
    )
    (net (code "93") (name "unconnected-(U3C-NC-PadF19)") (class "Default")
      (node (ref "U3") (pin "F19") (pinfunction "NC_F19") (pintype "passive"))
    )
    (net (code "94") (name "unconnected-(U3C-NC-PadG18)") (class "Default")
      (node (ref "U3") (pin "G18") (pinfunction "NC_G18") (pintype "passive"))
    )
    (net (code "95") (name "unconnected-(U3C-NC-PadG19)") (class "Default")
      (node (ref "U3") (pin "G19") (pinfunction "NC_G19") (pintype "passive"))
    )
    (net (code "96") (name "unconnected-(U3C-_NC-PadA1)") (class "Default")
      (node (ref "U3") (pin "A1") (pinfunction "_NC_A1") (pintype "passive"))
    )
    (net (code "97") (name "unconnected-(U3C-_NC-PadAA1)") (class "Default")
      (node (ref "U3") (pin "AA1") (pinfunction "_NC_AA1") (pintype "passive"))
    )
  )
)
